# tssop38p.net
KiCad netlist of a schematic drawn in EAGLE
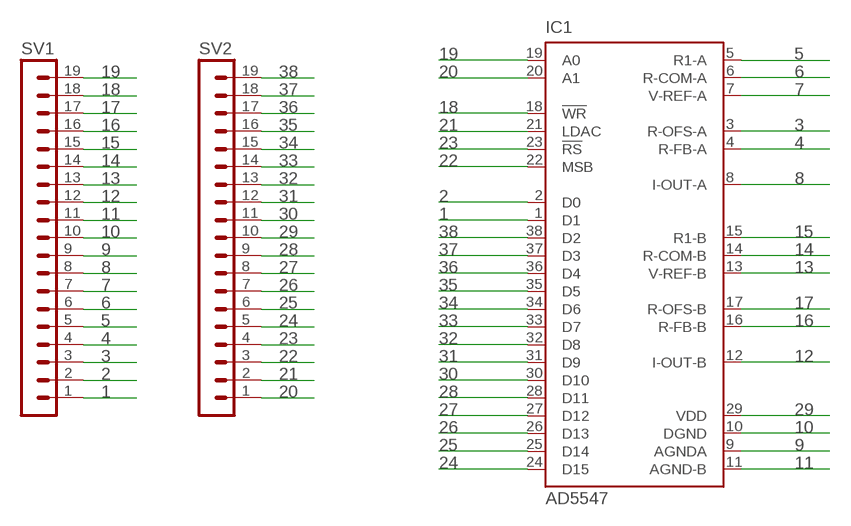
[diagram p0: schematic, sheet 1]

(export (version "E")
  (design (tool "Eeschema 10.0.6"))
  (components
    (comp (ref "IC1")
      (value "AD5547")
      (footprint "eagle-import:TSSOP38")
      (libsource (lib "eagle-import") (part "AD5547"))
    )
    (comp (ref "SV1")
      (value "MA19-1J")
      (footprint "eagle-import:MA19-1J")
      (libsource (lib "eagle-import") (part "MA19-1J"))
    )
    (comp (ref "SV2")
      (value "MA19-1J")
      (footprint "eagle-import:MA19-1J")
      (libsource (lib "eagle-import") (part "MA19-1J"))
    )
  )
  (nets
    (net (code "1") (name "/1") (class "Default")
      (node (ref "IC1") (pin "1") (pinfunction "D1_1") (pintype "input"))
      (node (ref "SV1") (pin "1") (pinfunction "1_1") (pintype "passive"))
    )
    (net (code "2") (name "/2") (class "Default")
      (node (ref "IC1") (pin "2") (pinfunction "D0_2") (pintype "input"))
      (node (ref "SV1") (pin "2") (pinfunction "2_2") (pintype "passive"))
    )
    (net (code "3") (name "/3") (class "Default")
      (node (ref "IC1") (pin "3") (pinfunction "R-OFS-A_3") (pintype "input"))
      (node (ref "SV1") (pin "3") (pinfunction "3_3") (pintype "passive"))
    )
    (net (code "4") (name "/4") (class "Default")
      (node (ref "IC1") (pin "4") (pinfunction "R-FB-A_4") (pintype "input"))
      (node (ref "SV1") (pin "4") (pinfunction "4_4") (pintype "passive"))
    )
    (net (code "5") (name "/5") (class "Default")
      (node (ref "IC1") (pin "5") (pinfunction "R1-A_5") (pintype "input"))
      (node (ref "SV1") (pin "5") (pinfunction "5_5") (pintype "passive"))
    )
    (net (code "6") (name "/6") (class "Default")
      (node (ref "IC1") (pin "6") (pinfunction "R-COM-A_6") (pintype "bidirectional"))
      (node (ref "SV1") (pin "6") (pinfunction "6_6") (pintype "passive"))
    )
    (net (code "7") (name "/7") (class "Default")
      (node (ref "IC1") (pin "7") (pinfunction "V-REF-A_7") (pintype "input"))
      (node (ref "SV1") (pin "7") (pinfunction "7_7") (pintype "passive"))
    )
    (net (code "8") (name "/8") (class "Default")
      (node (ref "IC1") (pin "8") (pinfunction "I-OUT-A_8") (pintype "output"))
      (node (ref "SV1") (pin "8") (pinfunction "8_8") (pintype "passive"))
    )
    (net (code "9") (name "/9") (class "Default")
      (node (ref "IC1") (pin "9") (pinfunction "AGNDA_9") (pintype "input"))
      (node (ref "SV1") (pin "9") (pinfunction "9_9") (pintype "passive"))
    )
    (net (code "10") (name "/10") (class "Default")
      (node (ref "IC1") (pin "10") (pinfunction "DGND_10") (pintype "input"))
      (node (ref "SV1") (pin "10") (pinfunction "10_10") (pintype "passive"))
    )
    (net (code "11") (name "/11") (class "Default")
      (node (ref "IC1") (pin "11") (pinfunction "AGND-B_11") (pintype "input"))
      (node (ref "SV1") (pin "11") (pinfunction "11_11") (pintype "passive"))
    )
    (net (code "12") (name "/12") (class "Default")
      (node (ref "IC1") (pin "12") (pinfunction "I-OUT-B_12") (pintype "output"))
      (node (ref "SV1") (pin "12") (pinfunction "12_12") (pintype "passive"))
    )
    (net (code "13") (name "/13") (class "Default")
      (node (ref "IC1") (pin "13") (pinfunction "V-REF-B_13") (pintype "input"))
      (node (ref "SV1") (pin "13") (pinfunction "13_13") (pintype "passive"))
    )
    (net (code "14") (name "/14") (class "Default")
      (node (ref "IC1") (pin "14") (pinfunction "R-COM-B_14") (pintype "bidirectional"))
      (node (ref "SV1") (pin "14") (pinfunction "14_14") (pintype "passive"))
    )
    (net (code "15") (name "/15") (class "Default")
      (node (ref "IC1") (pin "15") (pinfunction "R1-B_15") (pintype "input"))
      (node (ref "SV1") (pin "15") (pinfunction "15_15") (pintype "passive"))
    )
    (net (code "16") (name "/16") (class "Default")
      (node (ref "IC1") (pin "16") (pinfunction "R-FB-B_16") (pintype "input"))
      (node (ref "SV1") (pin "16") (pinfunction "16_16") (pintype "passive"))
    )
    (net (code "17") (name "/17") (class "Default")
      (node (ref "IC1") (pin "17") (pinfunction "R-OFS-B_17") (pintype "input"))
      (node (ref "SV1") (pin "17") (pinfunction "17_17") (pintype "passive"))
    )
    (net (code "18") (name "/18") (class "Default")
      (node (ref "IC1") (pin "18") (pinfunction "~{WR}_18") (pintype "input"))
      (node (ref "SV1") (pin "18") (pinfunction "18_18") (pintype "passive"))
    )
    (net (code "19") (name "/19") (class "Default")
      (node (ref "IC1") (pin "19") (pinfunction "A0_19") (pintype "input"))
      (node (ref "SV1") (pin "19") (pinfunction "19_19") (pintype "passive"))
    )
    (net (code "20") (name "/20") (class "Default")
      (node (ref "IC1") (pin "20") (pinfunction "A1_20") (pintype "input"))
      (node (ref "SV2") (pin "1") (pinfunction "1_1") (pintype "passive"))
    )
    (net (code "21") (name "/21") (class "Default")
      (node (ref "IC1") (pin "21") (pinfunction "LDAC_21") (pintype "input"))
      (node (ref "SV2") (pin "2") (pinfunction "2_2") (pintype "passive"))
    )
    (net (code "22") (name "/22") (class "Default")
      (node (ref "IC1") (pin "22") (pinfunction "MSB_22") (pintype "input"))
      (node (ref "SV2") (pin "3") (pinfunction "3_3") (pintype "passive"))
    )
    (net (code "23") (name "/23") (class "Default")
      (node (ref "IC1") (pin "23") (pinfunction "~{RS}_23") (pintype "input"))
      (node (ref "SV2") (pin "4") (pinfunction "4_4") (pintype "passive"))
    )
    (net (code "24") (name "/24") (class "Default")
      (node (ref "IC1") (pin "24") (pinfunction "D15_24") (pintype "input"))
      (node (ref "SV2") (pin "5") (pinfunction "5_5") (pintype "passive"))
    )
    (net (code "25") (name "/25") (class "Default")
      (node (ref "IC1") (pin "25") (pinfunction "D14_25") (pintype "input"))
      (node (ref "SV2") (pin "6") (pinfunction "6_6") (pintype "passive"))
    )
    (net (code "26") (name "/26") (class "Default")
      (node (ref "IC1") (pin "26") (pinfunction "D13_26") (pintype "input"))
      (node (ref "SV2") (pin "7") (pinfunction "7_7") (pintype "passive"))
    )
    (net (code "27") (name "/27") (class "Default")
      (node (ref "IC1") (pin "27") (pinfunction "D12_27") (pintype "input"))
      (node (ref "SV2") (pin "8") (pinfunction "8_8") (pintype "passive"))
    )
    (net (code "28") (name "/28") (class "Default")
      (node (ref "IC1") (pin "28") (pinfunction "D11_28") (pintype "input"))
      (node (ref "SV2") (pin "9") (pinfunction "9_9") (pintype "passive"))
    )
    (net (code "29") (name "/29") (class "Default")
      (node (ref "IC1") (pin "29") (pinfunction "VDD_29") (pintype "power_in"))
      (node (ref "SV2") (pin "10") (pinfunction "10_10") (pintype "passive"))
    )
    (net (code "30") (name "/30") (class "Default")
      (node (ref "IC1") (pin "30") (pinfunction "D10_30") (pintype "input"))
      (node (ref "SV2") (pin "11") (pinfunction "11_11") (pintype "passive"))
    )
    (net (code "31") (name "/31") (class "Default")
      (node (ref "IC1") (pin "31") (pinfunction "D9_31") (pintype "input"))
      (node (ref "SV2") (pin "12") (pinfunction "12_12") (pintype "passive"))
    )
    (net (code "32") (name "/32") (class "Default")
      (node (ref "IC1") (pin "32") (pinfunction "D8_32") (pintype "input"))
      (node (ref "SV2") (pin "13") (pinfunction "13_13") (pintype "passive"))
    )
    (net (code "33") (name "/33") (class "Default")
      (node (ref "IC1") (pin "33") (pinfunction "D7_33") (pintype "input"))
      (node (ref "SV2") (pin "14") (pinfunction "14_14") (pintype "passive"))
    )
    (net (code "34") (name "/34") (class "Default")
      (node (ref "IC1") (pin "34") (pinfunction "D6_34") (pintype "input"))
      (node (ref "SV2") (pin "15") (pinfunction "15_15") (pintype "passive"))
    )
    (net (code "35") (name "/35") (class "Default")
      (node (ref "IC1") (pin "35") (pinfunction "D5_35") (pintype "input"))
      (node (ref "SV2") (pin "16") (pinfunction "16_16") (pintype "passive"))
    )
    (net (code "36") (name "/36") (class "Default")
      (node (ref "IC1") (pin "36") (pinfunction "D4_36") (pintype "input"))
      (node (ref "SV2") (pin "17") (pinfunction "17_17") (pintype "passive"))
    )
    (net (code "37") (name "/37") (class "Default")
      (node (ref "IC1") (pin "37") (pinfunction "D3_37") (pintype "input"))
      (node (ref "SV2") (pin "18") (pinfunction "18_18") (pintype "passive"))
    )
    (net (code "38") (name "/38") (class "Default")
      (node (ref "IC1") (pin "38") (pinfunction "D2_38") (pintype "input"))
      (node (ref "SV2") (pin "19") (pinfunction "19_19") (pintype "passive"))
    )
  )
)
